# LB_BIT_i16_PULSE-v02_rev1.net
KiCad netlist of a schematic drawn in EAGLE
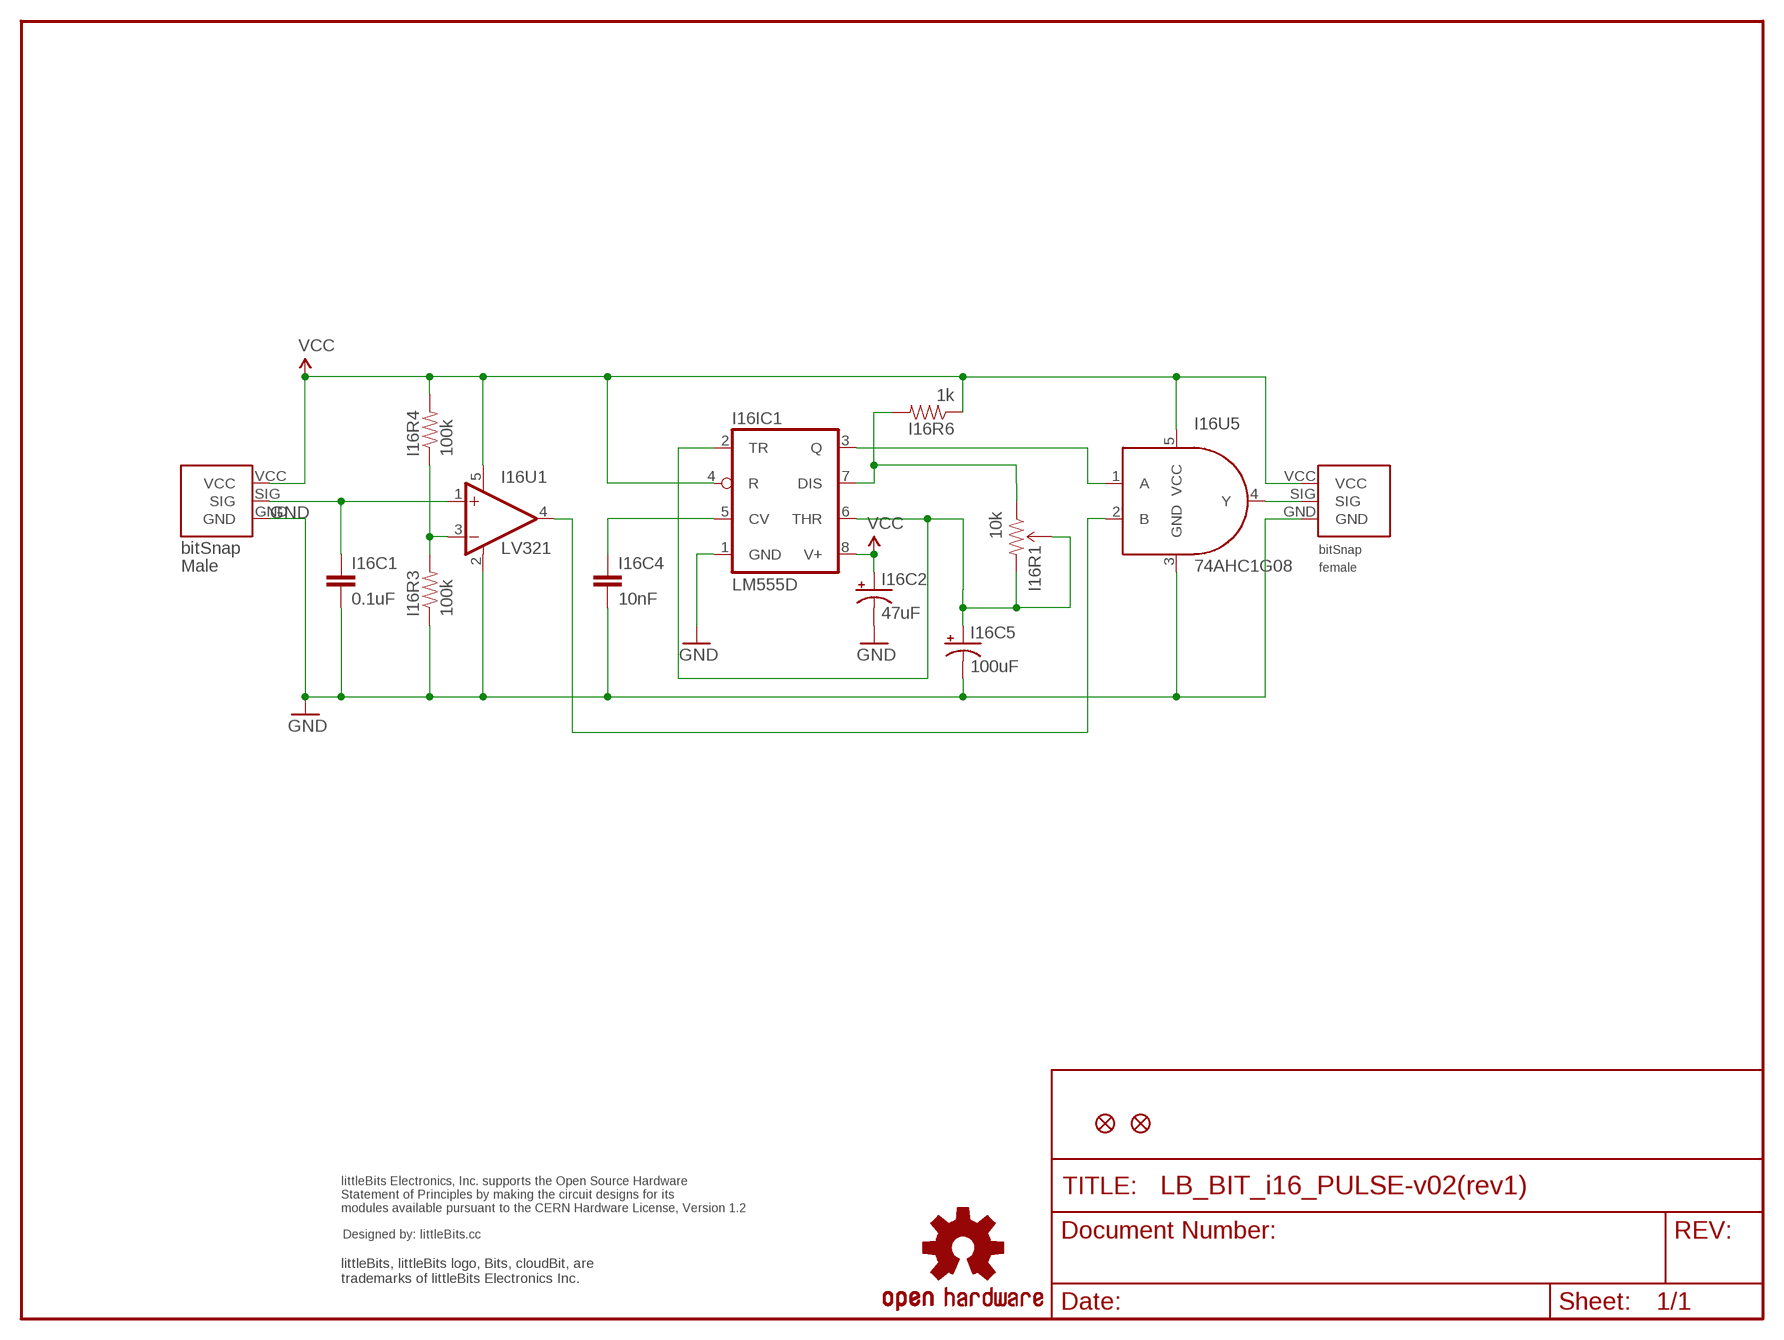
[diagram p0: schematic, sheet 1]

(export (version "E")
  (design (tool "Eeschema 10.0.6"))
  (components
    (comp (ref "I16BSF")
      (value "BITSNAP_FEMALE")
      (footprint "eagle-import:BITSNAP_FEMALE")
      (libsource (lib "eagle-import") (part "BITSNAP_FEMALE"))
    )
    (comp (ref "I16BSM")
      (value "BITSNAP_MALE")
      (footprint "eagle-import:BITSNAP_MALE")
      (libsource (lib "eagle-import") (part "BITSNAP_MALE"))
    )
    (comp (ref "I16C1")
      (value "0.1uF")
      (footprint "eagle-import:0603-CAP")
      (libsource (lib "eagle-import") (part "CAP0603-CAP"))
    )
    (comp (ref "I16C2")
      (value "47uF")
      (footprint "eagle-import:EIA3528")
      (libsource (lib "eagle-import") (part "CAP_POL3528"))
    )
    (comp (ref "I16C4")
      (value "10nF")
      (footprint "eagle-import:0603-CAP")
      (libsource (lib "eagle-import") (part "CAP0603-CAP"))
    )
    (comp (ref "I16C5")
      (value "100uF")
      (footprint "eagle-import:PANASONIC_C")
      (libsource (lib "eagle-import") (part "CAP_POLC"))
    )
    (comp (ref "I16IC1")
      (value "LM555D")
      (footprint "eagle-import:SO08")
      (libsource (lib "eagle-import") (part "555DLM"))
    )
    (comp (ref "I16R1")
      (value "10k")
      (footprint "eagle-import:TRIMPOT-3MM")
      (libsource (lib "eagle-import") (part "TRIMPOTSMD"))
    )
    (comp (ref "I16R3")
      (value "100k")
      (footprint "eagle-import:0603-RES")
      (libsource (lib "eagle-import") (part "RESISTOR0603-RES"))
    )
    (comp (ref "I16R4")
      (value "100k")
      (footprint "eagle-import:0603-RES")
      (libsource (lib "eagle-import") (part "RESISTOR0603-RES"))
    )
    (comp (ref "I16R6")
      (value "1k")
      (footprint "eagle-import:0603-RES")
      (libsource (lib "eagle-import") (part "RESISTOR0603-RES"))
    )
    (comp (ref "I16U1")
      (value "LV321")
      (footprint "eagle-import:SC70-5")
      (libsource (lib "eagle-import") (part "LV321"))
    )
    (comp (ref "I16U5")
      (value "74AHC1G08")
      (footprint "eagle-import:SOT23-5")
      (libsource (lib "eagle-import") (part "74AHC1G08"))
    )
    (comp (ref "JP1")
      (value "FIDUCIAL1X2.5")
      (footprint "eagle-import:FIDUCIAL-1X2.5")
      (libsource (lib "eagle-import") (part "FIDUCIAL1X2.5"))
    )
    (comp (ref "JP2")
      (value "FIDUCIAL1X2.5")
      (footprint "eagle-import:FIDUCIAL-1X2.5")
      (libsource (lib "eagle-import") (part "FIDUCIAL1X2.5"))
    )
    (comp (ref "U$1")
      (value "OSHWCREDIT")
      (footprint "eagle-import:OSHWCREDIT")
      (libsource (lib "eagle-import") (part "OSHWCREDIT"))
    )
    (comp (ref "U$5")
      (value "OSHW-LOGOL")
      (footprint "eagle-import:OSHW-LOGO-L")
      (libsource (lib "eagle-import") (part "OSHW-LOGOL"))
    )
  )
  (nets
    (net (code "1") (name "GND") (class "Default")
      (node (ref "I16BSF") (pin "GND") (pinfunction "GND_GND") (pintype "bidirectional"))
      (node (ref "I16BSM") (pin "GND") (pinfunction "GND_GND") (pintype "bidirectional"))
      (node (ref "I16C1") (pin "2") (pinfunction "2_2") (pintype "passive"))
      (node (ref "I16C2") (pin "C") (pinfunction "-_C") (pintype "passive"))
      (node (ref "I16C4") (pin "2") (pinfunction "2_2") (pintype "passive"))
      (node (ref "I16C5") (pin "-") (pinfunction "-_-") (pintype "passive"))
      (node (ref "I16IC1") (pin "1") (pinfunction "GND_1") (pintype "power_in"))
      (node (ref "I16R3") (pin "1") (pinfunction "1_1") (pintype "passive"))
      (node (ref "I16U1") (pin "2") (pinfunction "V-_2") (pintype "power_in"))
      (node (ref "I16U5") (pin "3") (pinfunction "GND_3") (pintype "bidirectional"))
    )
    (net (code "2") (name "Net-(I16IC1-CV)") (class "Default")
      (node (ref "I16C4") (pin "1") (pinfunction "1_1") (pintype "passive"))
      (node (ref "I16IC1") (pin "5") (pinfunction "CV_5") (pintype "input"))
    )
    (net (code "3") (name "Net-(I16IC1-DIS)") (class "Default")
      (node (ref "I16IC1") (pin "7") (pinfunction "DIS_7") (pintype "input"))
      (node (ref "I16R1") (pin "1") (pinfunction "CCW_1") (pintype "passive"))
      (node (ref "I16R6") (pin "2") (pinfunction "2_2") (pintype "passive"))
    )
    (net (code "4") (name "Net-(I16IC1-Q)") (class "Default")
      (node (ref "I16IC1") (pin "3") (pinfunction "Q_3") (pintype "output"))
      (node (ref "I16U5") (pin "1") (pinfunction "A_1") (pintype "bidirectional"))
    )
    (net (code "5") (name "Net-(I16IC1-THR)") (class "Default")
      (node (ref "I16C5") (pin "+") (pinfunction "+_+") (pintype "passive"))
      (node (ref "I16IC1") (pin "2") (pinfunction "TR_2") (pintype "input"))
      (node (ref "I16IC1") (pin "6") (pinfunction "THR_6") (pintype "input"))
      (node (ref "I16R1") (pin "2") (pinfunction "WIPER_2") (pintype "passive"))
      (node (ref "I16R1") (pin "3") (pinfunction "CW_3") (pintype "passive"))
    )
    (net (code "6") (name "Net-(I16U1-+IN)") (class "Default")
      (node (ref "I16BSM") (pin "SIG") (pinfunction "SIG_SIG") (pintype "bidirectional"))
      (node (ref "I16C1") (pin "1") (pinfunction "1_1") (pintype "passive"))
      (node (ref "I16U1") (pin "1") (pinfunction "+IN_1") (pintype "input"))
    )
    (net (code "7") (name "Net-(I16U1--IN)") (class "Default")
      (node (ref "I16R3") (pin "2") (pinfunction "2_2") (pintype "passive"))
      (node (ref "I16R4") (pin "1") (pinfunction "1_1") (pintype "passive"))
      (node (ref "I16U1") (pin "3") (pinfunction "-IN_3") (pintype "input"))
    )
    (net (code "8") (name "Net-(I16U1-OUT)") (class "Default")
      (node (ref "I16U1") (pin "4") (pinfunction "OUT_4") (pintype "output"))
      (node (ref "I16U5") (pin "2") (pinfunction "B_2") (pintype "bidirectional"))
    )
    (net (code "9") (name "Net-(I16U5-Y)") (class "Default")
      (node (ref "I16BSF") (pin "SIG") (pinfunction "SIG_SIG") (pintype "bidirectional"))
      (node (ref "I16U5") (pin "4") (pinfunction "Y_4") (pintype "bidirectional"))
    )
    (net (code "10") (name "VCC") (class "Default")
      (node (ref "I16BSF") (pin "VCC") (pinfunction "VCC_VCC") (pintype "bidirectional"))
      (node (ref "I16BSM") (pin "VCC") (pinfunction "VCC_VCC") (pintype "bidirectional"))
      (node (ref "I16C2") (pin "A") (pinfunction "+_A") (pintype "passive"))
      (node (ref "I16IC1") (pin "4") (pinfunction "R_4") (pintype "input"))
      (node (ref "I16IC1") (pin "8") (pinfunction "V+_8") (pintype "power_in"))
      (node (ref "I16R4") (pin "2") (pinfunction "2_2") (pintype "passive"))
      (node (ref "I16R6") (pin "1") (pinfunction "1_1") (pintype "passive"))
      (node (ref "I16U1") (pin "5") (pinfunction "V+_5") (pintype "power_in"))
      (node (ref "I16U5") (pin "5") (pinfunction "VCC_5") (pintype "bidirectional"))
    )
  )
)
